# USB_Device.net
KiCad netlist of a schematic drawn in Altium Designer
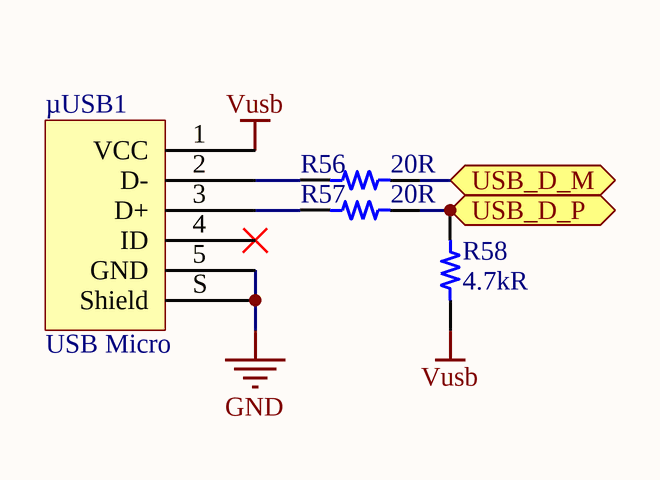
[diagram p0: USB Device.SchDoc]

(export (version "E")
  (design (tool "Eeschema 10.0.6"))
  (components
    (comp (ref "R56")
      (value "20R")
      (footprint "RES 0603/1608")
      (description "Ceramic, SMT Capacitor")
      (fields
        (field (name "MANUFACTURER") "Panasonic")
        (field (name "MANUFACTURER PART NUMBER") "ERJ3EKF20R0V")
      )
      (libsource (lib "yildizIoT Library") (part "Resistor_Chip"))
    )
    (comp (ref "R57")
      (value "20R")
      (footprint "RES 0603/1608")
      (description "Ceramic, SMT Capacitor")
      (fields
        (field (name "MANUFACTURER") "Panasonic")
        (field (name "MANUFACTURER PART NUMBER") "ERJ3EKF20R0V")
      )
      (libsource (lib "yildizIoT Library") (part "Resistor_Chip"))
    )
    (comp (ref "R58")
      (value "4.7kR")
      (footprint "RES 0603/1608")
      (description "Ceramic, SMT Capacitor")
      (fields
        (field (name "MANUFACTURER") "Yageo Phycomp")
        (field (name "MANUFACTURER PART NUMBER") "RC0603FR-074K7L")
      )
      (libsource (lib "yildizIoT Library") (part "Resistor_Chip"))
    )
    (comp (ref "µUSB1")
      (value "USB Micro")
      (footprint "FCI USB 10118193-0001LF")
      (libsource (lib "yildizIoT Library") (part "USB 2.0 Type B Micro"))
    )
  )
  (nets
    (net (code "1") (name "/USB_D_M") (class "Default")
      (node (ref "R56") (pin "1") (pinfunction "1_1") (pintype "passive"))
    )
    (net (code "2") (name "/USB_D_P") (class "Default")
      (node (ref "R57") (pin "1") (pinfunction "1_1") (pintype "passive"))
      (node (ref "R58") (pin "2") (pinfunction "2_2") (pintype "passive"))
    )
    (net (code "3") (name "GND") (class "Default")
      (node (ref "µUSB1") (pin "5") (pinfunction "GND_5") (pintype "passive"))
      (node (ref "µUSB1") (pin "S") (pinfunction "Shield_S") (pintype "passive"))
    )
    (net (code "4") (name "Net-(µUSB1-D+)") (class "Default")
      (node (ref "R57") (pin "2") (pinfunction "2_2") (pintype "passive"))
      (node (ref "µUSB1") (pin "3") (pinfunction "D+_3") (pintype "passive"))
    )
    (net (code "5") (name "Net-(µUSB1-D-)") (class "Default")
      (node (ref "R56") (pin "2") (pinfunction "2_2") (pintype "passive"))
      (node (ref "µUSB1") (pin "2") (pinfunction "D-_2") (pintype "passive"))
    )
    (net (code "6") (name "Vusb") (class "Default")
      (node (ref "R58") (pin "1") (pinfunction "1_1") (pintype "passive"))
      (node (ref "µUSB1") (pin "1") (pinfunction "VCC_1") (pintype "passive"))
    )
    (net (code "7") (name "unconnected-(µUSB1-ID-Pad4)") (class "Default")
      (node (ref "µUSB1") (pin "4") (pinfunction "ID_4") (pintype "passive+no_connect"))
    )
  )
)
